# rgb_and_irdistance_side3.net
KiCad netlist of a schematic drawn in EAGLE
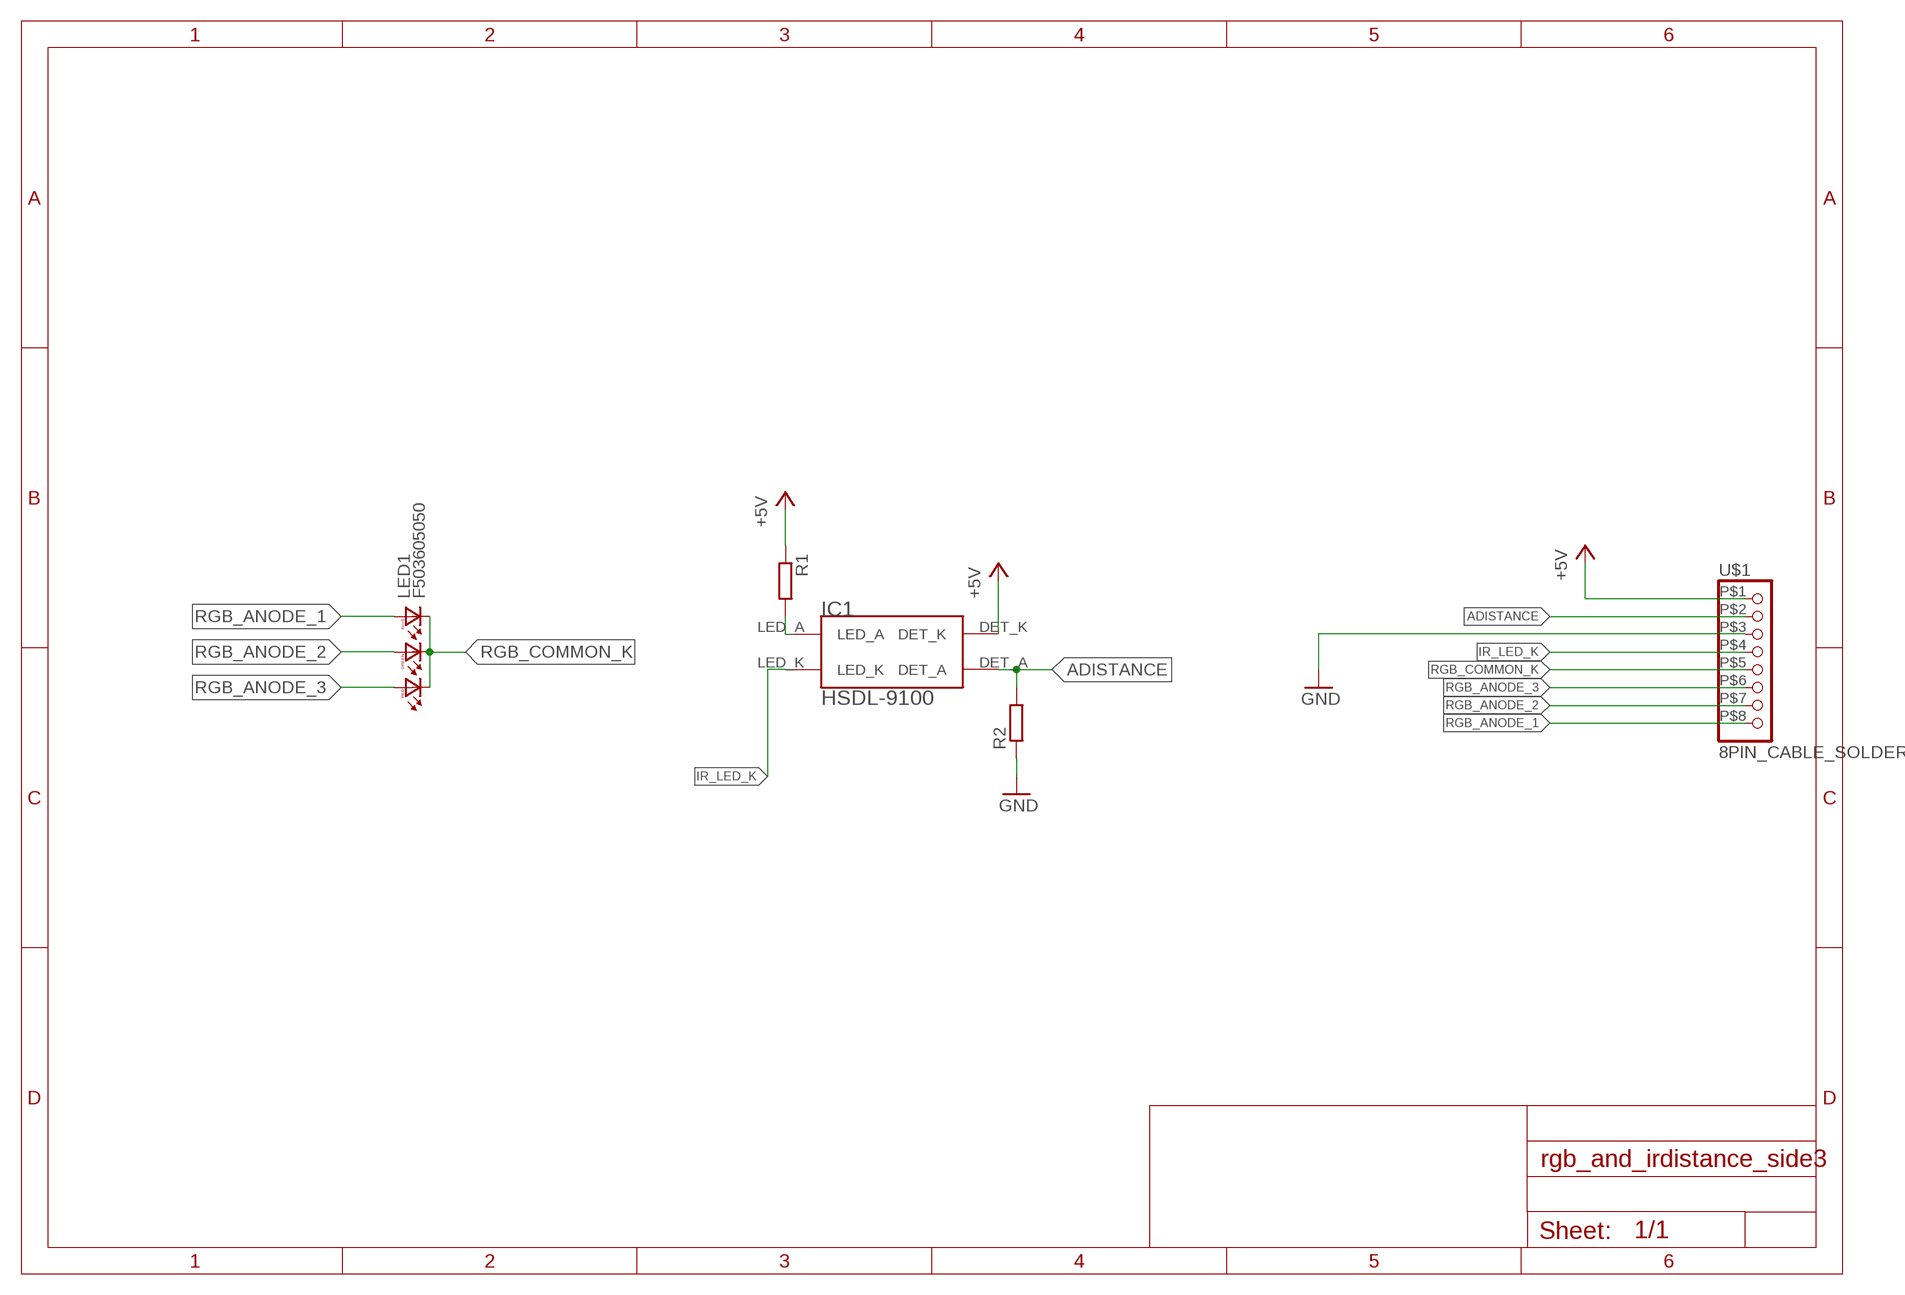
[diagram p0: schematic, sheet 1]

(export (version "E")
  (design (tool "Eeschema 10.0.6"))
  (components
    (comp (ref "IC1")
      (value "HSDL-9100")
      (footprint "eagle-import:HSDL-9100")
      (libsource (lib "eagle-import") (part "HSDL-9100"))
    )
    (comp (ref "LED1")
      (value "F503605050")
      (footprint "eagle-import:5050LED")
      (libsource (lib "eagle-import") (part "F503605050"))
    )
    (comp (ref "R1")
      (value "R-EU_M0805")
      (footprint "eagle-import:M0805")
      (libsource (lib "eagle-import") (part "R-EU_M0805"))
    )
    (comp (ref "R2")
      (value "R-EU_M0805")
      (footprint "eagle-import:M0805")
      (libsource (lib "eagle-import") (part "R-EU_M0805"))
    )
    (comp (ref "U$1")
      (value "8PIN_CABLE_SOLDER")
      (footprint "eagle-import:8PIN_CABLE_SOLDER")
      (libsource (lib "eagle-import") (part "8PIN_CABLE_SOLDER"))
    )
  )
  (nets
    (net (code "1") (name "+5V") (class "Default")
      (node (ref "IC1") (pin "DET_K") (pinfunction "DET_K_DET_K") (pintype "bidirectional"))
      (node (ref "R1") (pin "1") (pinfunction "1_1") (pintype "passive"))
      (node (ref "U$1") (pin "P$1") (pinfunction "1_P$1") (pintype "passive"))
    )
    (net (code "2") (name "ADISTANCE") (class "Default")
      (node (ref "IC1") (pin "DET_A") (pinfunction "DET_A_DET_A") (pintype "bidirectional"))
      (node (ref "R2") (pin "2") (pinfunction "2_2") (pintype "passive"))
      (node (ref "U$1") (pin "P$2") (pinfunction "2_P$2") (pintype "passive"))
    )
    (net (code "3") (name "GND") (class "Default")
      (node (ref "R2") (pin "1") (pinfunction "1_1") (pintype "passive"))
      (node (ref "U$1") (pin "P$3") (pinfunction "3_P$3") (pintype "passive"))
    )
    (net (code "4") (name "IR_LED_K") (class "Default")
      (node (ref "IC1") (pin "LED_K") (pinfunction "LED_K_LED_K") (pintype "bidirectional"))
      (node (ref "U$1") (pin "P$4") (pinfunction "4_P$4") (pintype "passive"))
    )
    (net (code "5") (name "Net-(IC1-PadLED_A)") (class "Default")
      (node (ref "IC1") (pin "LED_A") (pinfunction "LED_A_LED_A") (pintype "bidirectional"))
      (node (ref "R1") (pin "2") (pinfunction "2_2") (pintype "passive"))
    )
    (net (code "6") (name "RGB_ANODE_1") (class "Default")
      (node (ref "LED1") (pin "B1") (pinfunction "BA_B1") (pintype "passive"))
      (node (ref "U$1") (pin "P$8") (pinfunction "8_P$8") (pintype "passive"))
    )
    (net (code "7") (name "RGB_ANODE_2") (class "Default")
      (node (ref "LED1") (pin "G1") (pinfunction "GA_G1") (pintype "passive"))
      (node (ref "U$1") (pin "P$7") (pinfunction "7_P$7") (pintype "passive"))
    )
    (net (code "8") (name "RGB_ANODE_3") (class "Default")
      (node (ref "LED1") (pin "R1") (pinfunction "RA_R1") (pintype "passive"))
      (node (ref "U$1") (pin "P$6") (pinfunction "6_P$6") (pintype "passive"))
    )
    (net (code "9") (name "RGB_COMMON_K") (class "Default")
      (node (ref "LED1") (pin "B2") (pinfunction "BC_B2") (pintype "passive"))
      (node (ref "LED1") (pin "G2") (pinfunction "GC_G2") (pintype "passive"))
      (node (ref "LED1") (pin "R2") (pinfunction "RC_R2") (pintype "passive"))
      (node (ref "U$1") (pin "P$5") (pinfunction "5_P$5") (pintype "passive"))
    )
  )
)
